# Status.net
KiCad netlist of a schematic drawn in Altium Designer
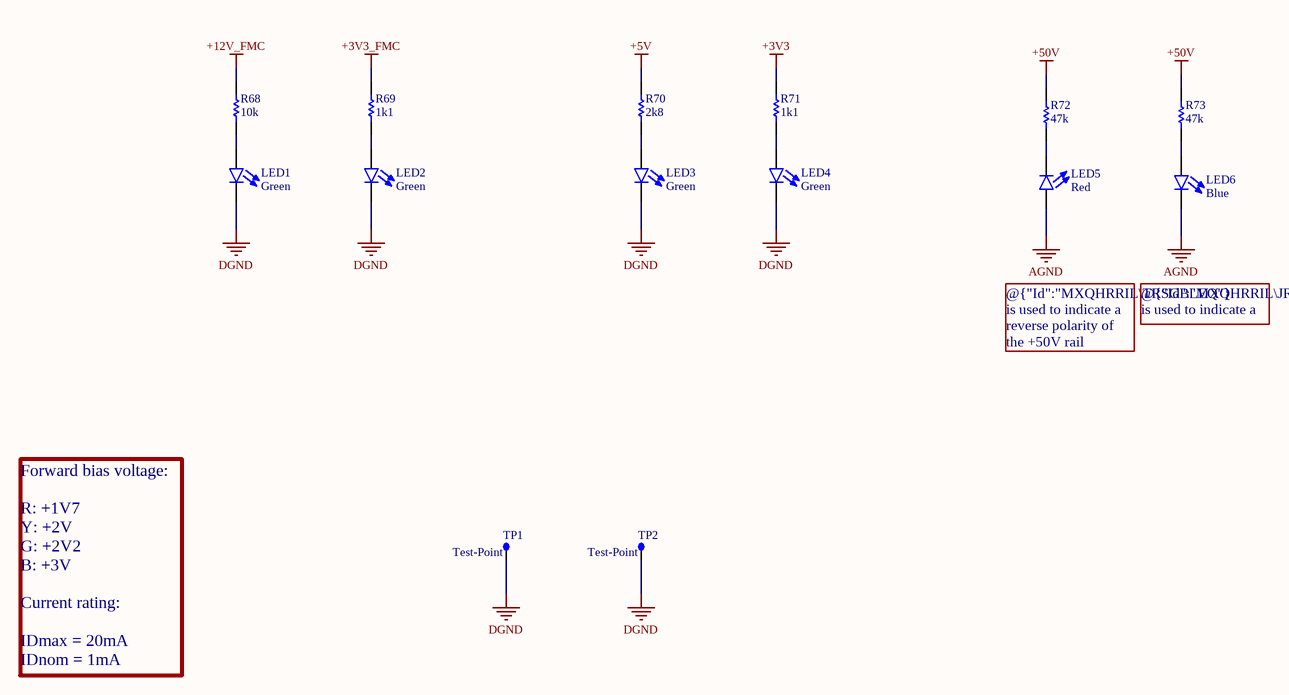
[diagram p0: Status.SchDoc]

(export (version "E")
  (design (tool "Eeschema 10.0.6"))
  (components
    (comp (ref "LED1") (value "Green") (footprint "RES_0603") (libsource (lib "IIS-Lib_TW") (part "LED")))
    (comp (ref "LED2") (value "Green") (footprint "RES_0603") (libsource (lib "IIS-Lib_TW") (part "LED")))
    (comp (ref "LED3") (value "Green") (footprint "RES_0603") (libsource (lib "IIS-Lib_TW") (part "LED")))
    (comp (ref "LED4") (value "Green") (footprint "RES_0603") (libsource (lib "IIS-Lib_TW") (part "LED")))
    (comp (ref "LED5") (value "Red") (footprint "RES_0603") (libsource (lib "IIS-Lib_TW") (part "LED")))
    (comp (ref "LED6") (value "Blue") (footprint "RES_0603") (libsource (lib "IIS-Lib_TW") (part "LED")))
    (comp (ref "R68") (value "10k") (footprint "RES_0402") (libsource (lib "IIS-Lib_TW") (part "Res")))
    (comp (ref "R69") (value "1k1") (footprint "RES_0402") (libsource (lib "IIS-Lib_TW") (part "Res")))
    (comp (ref "R70") (value "2k8") (footprint "RES_0402") (libsource (lib "IIS-Lib_TW") (part "Res")))
    (comp (ref "R71") (value "1k1") (footprint "RES_0402") (libsource (lib "IIS-Lib_TW") (part "Res")))
    (comp (ref "R72") (value "47k") (footprint "RES_0402") (libsource (lib "IIS-Lib_TW") (part "Res")))
    (comp (ref "R73") (value "47k") (footprint "RES_0402") (libsource (lib "IIS-Lib_TW") (part "Res")))
    (comp (ref "TP1")
      (value "Test-Point")
      (footprint "Test-Point-2")
      (description "Generic Test Point")
      (libsource (lib "IIS-Lib_TW") (part "Test-Point"))
    )
    (comp (ref "TP2")
      (value "Test-Point")
      (footprint "Test-Point-2")
      (description "Generic Test Point")
      (libsource (lib "IIS-Lib_TW") (part "Test-Point"))
    )
  )
  (nets
    (net (code "1") (name "+3V3") (class "Default")
      (node (ref "R71") (pin "2") (pinfunction "2_2") (pintype "passive"))
    )
    (net (code "2") (name "+3V3_FMC") (class "Default")
      (node (ref "R69") (pin "2") (pinfunction "2_2") (pintype "passive"))
    )
    (net (code "3") (name "+5V") (class "Default")
      (node (ref "R70") (pin "2") (pinfunction "2_2") (pintype "passive"))
    )
    (net (code "4") (name "+12V_FMC") (class "Default")
      (node (ref "R68") (pin "2") (pinfunction "2_2") (pintype "passive"))
    )
    (net (code "5") (name "+50V") (class "Default")
      (node (ref "R72") (pin "2") (pinfunction "2_2") (pintype "passive"))
      (node (ref "R73") (pin "2") (pinfunction "2_2") (pintype "passive"))
    )
    (net (code "6") (name "AGND") (class "Default")
      (node (ref "LED5") (pin "1") (pinfunction "1_1") (pintype "passive"))
      (node (ref "LED6") (pin "2") (pinfunction "2_2") (pintype "passive"))
    )
    (net (code "7") (name "DGND") (class "Default")
      (node (ref "LED1") (pin "2") (pinfunction "2_2") (pintype "passive"))
      (node (ref "LED2") (pin "2") (pinfunction "2_2") (pintype "passive"))
      (node (ref "LED3") (pin "2") (pinfunction "2_2") (pintype "passive"))
      (node (ref "LED4") (pin "2") (pinfunction "2_2") (pintype "passive"))
      (node (ref "TP1") (pin "1") (pinfunction "TP_1") (pintype "passive"))
      (node (ref "TP2") (pin "1") (pinfunction "TP_1") (pintype "passive"))
    )
    (net (code "8") (name "Net-(LED1-Pad1)") (class "Default")
      (node (ref "LED1") (pin "1") (pinfunction "1_1") (pintype "passive"))
      (node (ref "R68") (pin "1") (pinfunction "1_1") (pintype "passive"))
    )
    (net (code "9") (name "Net-(LED2-Pad1)") (class "Default")
      (node (ref "LED2") (pin "1") (pinfunction "1_1") (pintype "passive"))
      (node (ref "R69") (pin "1") (pinfunction "1_1") (pintype "passive"))
    )
    (net (code "10") (name "Net-(LED3-Pad1)") (class "Default")
      (node (ref "LED3") (pin "1") (pinfunction "1_1") (pintype "passive"))
      (node (ref "R70") (pin "1") (pinfunction "1_1") (pintype "passive"))
    )
    (net (code "11") (name "Net-(LED4-Pad1)") (class "Default")
      (node (ref "LED4") (pin "1") (pinfunction "1_1") (pintype "passive"))
      (node (ref "R71") (pin "1") (pinfunction "1_1") (pintype "passive"))
    )
    (net (code "12") (name "Net-(LED5-Pad2)") (class "Default")
      (node (ref "LED5") (pin "2") (pinfunction "2_2") (pintype "passive"))
      (node (ref "R72") (pin "1") (pinfunction "1_1") (pintype "passive"))
    )
    (net (code "13") (name "Net-(LED6-Pad1)") (class "Default")
      (node (ref "LED6") (pin "1") (pinfunction "1_1") (pintype "passive"))
      (node (ref "R73") (pin "1") (pinfunction "1_1") (pintype "passive"))
    )
  )
)
